# CPU.net
KiCad netlist of a schematic drawn in EAGLE
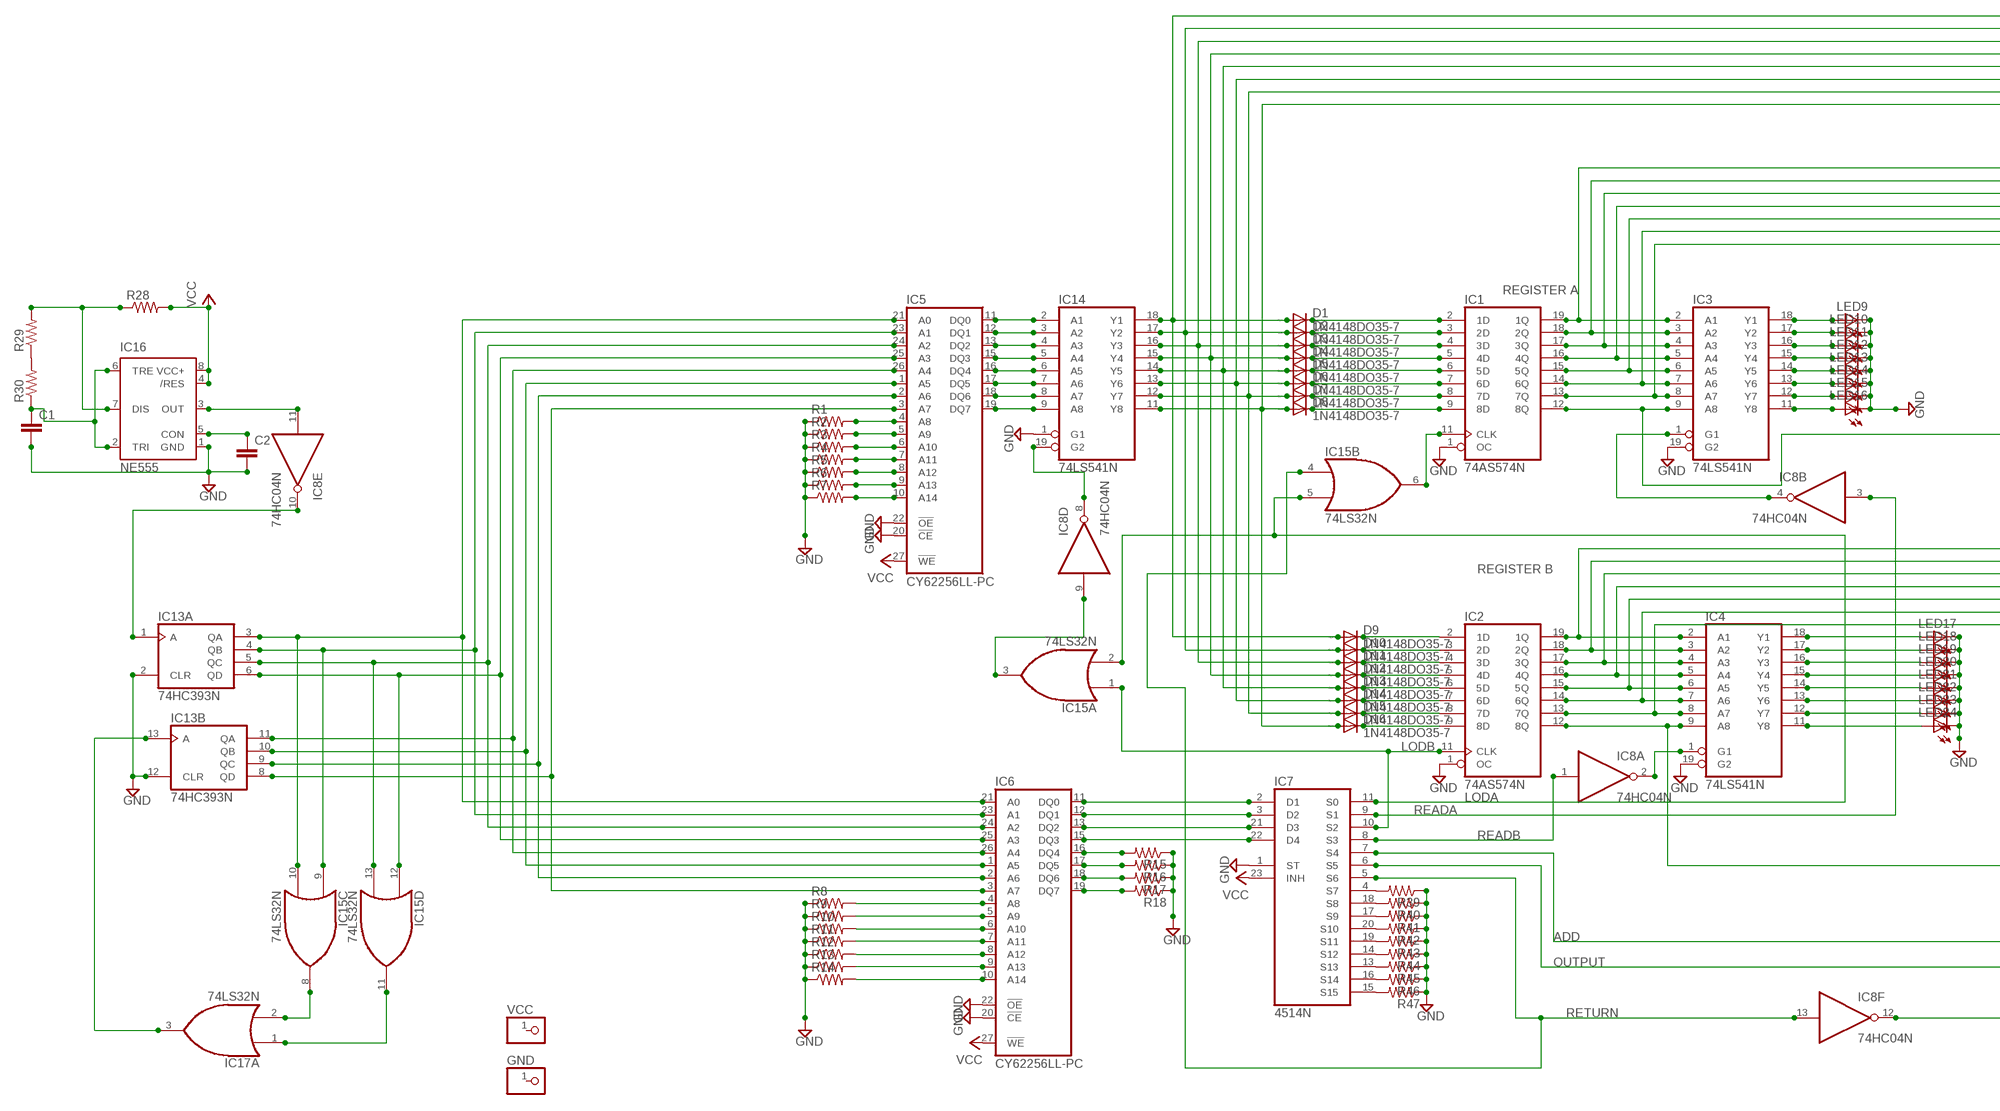
[diagram p0: schematic, sheet 1, part 1 of 2]
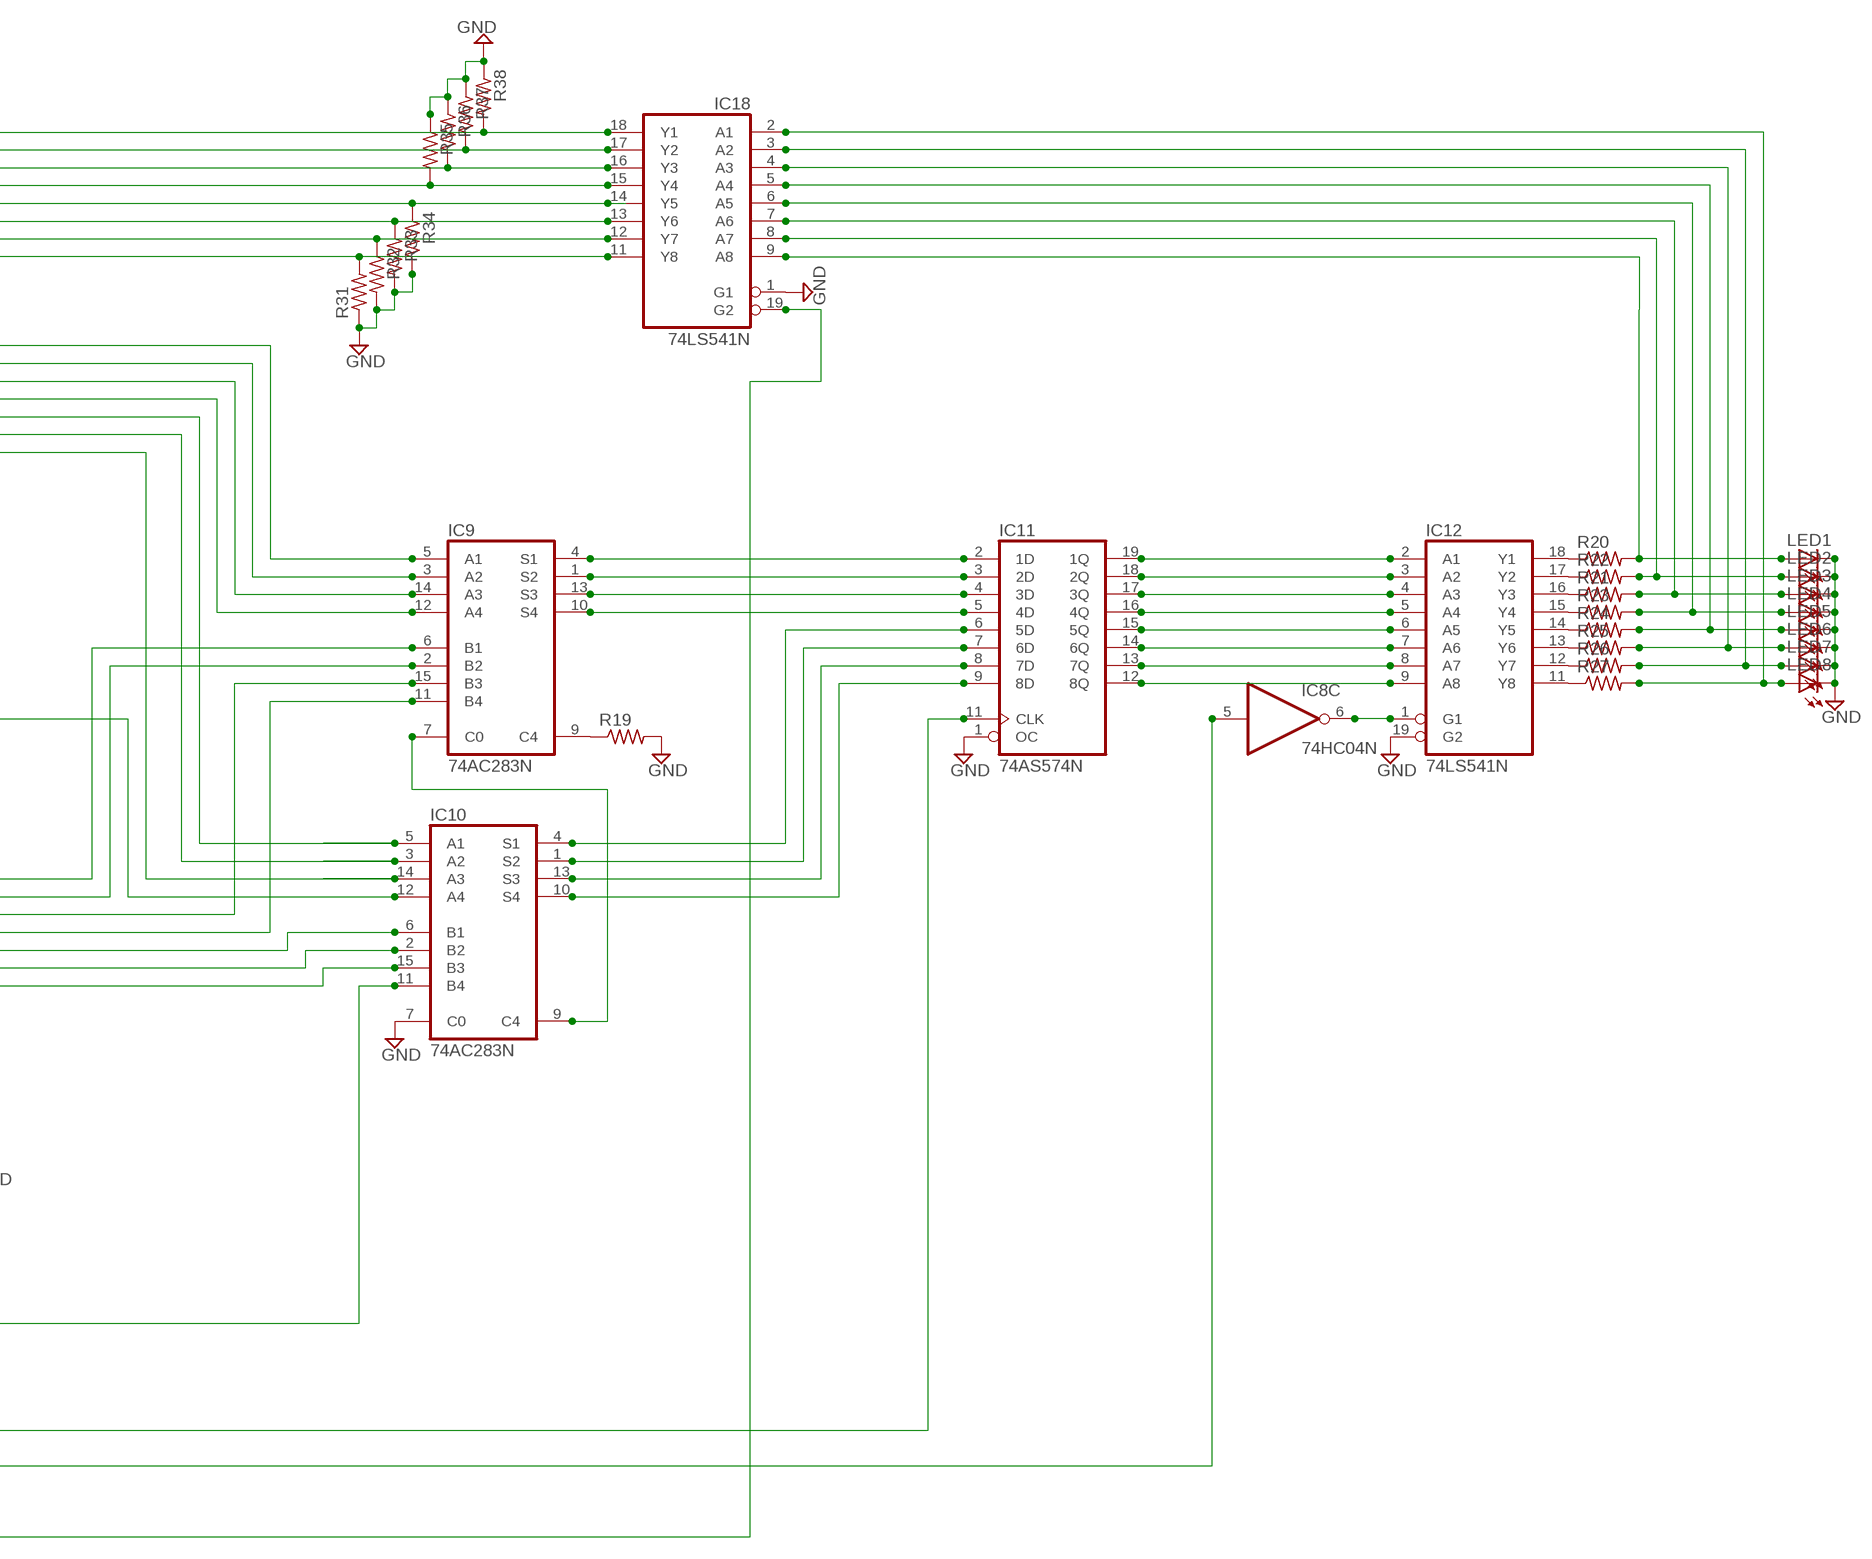
[diagram p1: schematic, sheet 1, part 2 of 2]

(export (version "E")
  (design (tool "Eeschema 10.0.6"))
  (components
    (comp (ref "C1")
      (value "C2,5-3")
      (footprint "eagle-import:C2.5-3")
      (libsource (lib "eagle-import") (part "C2,5-3"))
    )
    (comp (ref "C2")
      (value "C2,5-3")
      (footprint "eagle-import:C2.5-3")
      (libsource (lib "eagle-import") (part "C2,5-3"))
    )
    (comp (ref "D1")
      (value "1N4148DO35-7")
      (footprint "eagle-import:DO35-7")
      (libsource (lib "eagle-import") (part "1N4148DO35-7"))
    )
    (comp (ref "D2")
      (value "1N4148DO35-7")
      (footprint "eagle-import:DO35-7")
      (libsource (lib "eagle-import") (part "1N4148DO35-7"))
    )
    (comp (ref "D3")
      (value "1N4148DO35-7")
      (footprint "eagle-import:DO35-7")
      (libsource (lib "eagle-import") (part "1N4148DO35-7"))
    )
    (comp (ref "D4")
      (value "1N4148DO35-7")
      (footprint "eagle-import:DO35-7")
      (libsource (lib "eagle-import") (part "1N4148DO35-7"))
    )
    (comp (ref "D5")
      (value "1N4148DO35-7")
      (footprint "eagle-import:DO35-7")
      (libsource (lib "eagle-import") (part "1N4148DO35-7"))
    )
    (comp (ref "D6")
      (value "1N4148DO35-7")
      (footprint "eagle-import:DO35-7")
      (libsource (lib "eagle-import") (part "1N4148DO35-7"))
    )
    (comp (ref "D7")
      (value "1N4148DO35-7")
      (footprint "eagle-import:DO35-7")
      (libsource (lib "eagle-import") (part "1N4148DO35-7"))
    )
    (comp (ref "D8")
      (value "1N4148DO35-7")
      (footprint "eagle-import:DO35-7")
      (libsource (lib "eagle-import") (part "1N4148DO35-7"))
    )
    (comp (ref "D9")
      (value "1N4148DO35-7")
      (footprint "eagle-import:DO35-7")
      (libsource (lib "eagle-import") (part "1N4148DO35-7"))
    )
    (comp (ref "D10")
      (value "1N4148DO35-7")
      (footprint "eagle-import:DO35-7")
      (libsource (lib "eagle-import") (part "1N4148DO35-7"))
    )
    (comp (ref "D11")
      (value "1N4148DO35-7")
      (footprint "eagle-import:DO35-7")
      (libsource (lib "eagle-import") (part "1N4148DO35-7"))
    )
    (comp (ref "D12")
      (value "1N4148DO35-7")
      (footprint "eagle-import:DO35-7")
      (libsource (lib "eagle-import") (part "1N4148DO35-7"))
    )
    (comp (ref "D13")
      (value "1N4148DO35-7")
      (footprint "eagle-import:DO35-7")
      (libsource (lib "eagle-import") (part "1N4148DO35-7"))
    )
    (comp (ref "D14")
      (value "1N4148DO35-7")
      (footprint "eagle-import:DO35-7")
      (libsource (lib "eagle-import") (part "1N4148DO35-7"))
    )
    (comp (ref "D15")
      (value "1N4148DO35-7")
      (footprint "eagle-import:DO35-7")
      (libsource (lib "eagle-import") (part "1N4148DO35-7"))
    )
    (comp (ref "D16")
      (value "1N4148DO35-7")
      (footprint "eagle-import:DO35-7")
      (libsource (lib "eagle-import") (part "1N4148DO35-7"))
    )
    (comp (ref "GND")
      (value "PINHD-1X1")
      (footprint "eagle-import:1X01")
      (libsource (lib "eagle-import") (part "PINHD-1X1"))
    )
    (comp (ref "IC1")
      (value "74AS574N")
      (footprint "eagle-import:DIL20")
      (libsource (lib "eagle-import") (part "74574NAS"))
    )
    (comp (ref "IC2")
      (value "74AS574N")
      (footprint "eagle-import:DIL20")
      (libsource (lib "eagle-import") (part "74574NAS"))
    )
    (comp (ref "IC3")
      (value "74LS541N")
      (footprint "eagle-import:DIL20")
      (libsource (lib "eagle-import") (part "74541NLS"))
    )
    (comp (ref "IC4")
      (value "74LS541N")
      (footprint "eagle-import:DIL20")
      (libsource (lib "eagle-import") (part "74541NLS"))
    )
    (comp (ref "IC5")
      (value "CY62256LL-PC")
      (footprint "eagle-import:DIL28-6")
      (libsource (lib "eagle-import") (part "CY62256LL-?PC"))
    )
    (comp (ref "IC6")
      (value "CY62256LL-PC")
      (footprint "eagle-import:DIL28-6")
      (libsource (lib "eagle-import") (part "CY62256LL-?PC"))
    )
    (comp (ref "IC7")
      (value "4514N")
      (footprint "eagle-import:DIL24-6")
      (libsource (lib "eagle-import") (part "4514N"))
    )
    (comp (ref "IC8")
      (value "74HC04N")
      (footprint "eagle-import:DIL14")
      (libsource (lib "eagle-import") (part "7404NHC"))
    )
    (comp (ref "IC9")
      (value "74AC283N")
      (footprint "eagle-import:DIL16")
      (libsource (lib "eagle-import") (part "74283NAC"))
    )
    (comp (ref "IC10")
      (value "74AC283N")
      (footprint "eagle-import:DIL16")
      (libsource (lib "eagle-import") (part "74283NAC"))
    )
    (comp (ref "IC11")
      (value "74AS574N")
      (footprint "eagle-import:DIL20")
      (libsource (lib "eagle-import") (part "74574NAS"))
    )
    (comp (ref "IC12")
      (value "74LS541N")
      (footprint "eagle-import:DIL20")
      (libsource (lib "eagle-import") (part "74541NLS"))
    )
    (comp (ref "IC13")
      (value "74HC393N")
      (footprint "eagle-import:DIL14")
      (libsource (lib "eagle-import") (part "74393NHC"))
    )
    (comp (ref "IC14")
      (value "74LS541N")
      (footprint "eagle-import:DIL20")
      (libsource (lib "eagle-import") (part "74541NLS"))
    )
    (comp (ref "IC15")
      (value "74LS32N")
      (footprint "eagle-import:DIL14")
      (libsource (lib "eagle-import") (part "7432NLS"))
    )
    (comp (ref "IC16")
      (value "NE555")
      (footprint "eagle-import:DIL-08")
      (fields (field (name "MF") "Arrow Electronics") (field (name "MPN") "NE555N"))
      (libsource (lib "eagle-import") (part "NE555"))
    )
    (comp (ref "IC17")
      (value "74LS32N")
      (footprint "eagle-import:DIL14")
      (libsource (lib "eagle-import") (part "7432NLS"))
    )
    (comp (ref "IC18")
      (value "74LS541N")
      (footprint "eagle-import:DIL20")
      (libsource (lib "eagle-import") (part "74541NLS"))
    )
    (comp (ref "LED1")
      (value "LED3MM")
      (footprint "eagle-import:LED3MM")
      (libsource (lib "eagle-import") (part "LED3MM"))
    )
    (comp (ref "LED2")
      (value "LED3MM")
      (footprint "eagle-import:LED3MM")
      (libsource (lib "eagle-import") (part "LED3MM"))
    )
    (comp (ref "LED3")
      (value "LED3MM")
      (footprint "eagle-import:LED3MM")
      (libsource (lib "eagle-import") (part "LED3MM"))
    )
    (comp (ref "LED4")
      (value "LED3MM")
      (footprint "eagle-import:LED3MM")
      (libsource (lib "eagle-import") (part "LED3MM"))
    )
    (comp (ref "LED5")
      (value "LED3MM")
      (footprint "eagle-import:LED3MM")
      (libsource (lib "eagle-import") (part "LED3MM"))
    )
    (comp (ref "LED6")
      (value "LED3MM")
      (footprint "eagle-import:LED3MM")
      (libsource (lib "eagle-import") (part "LED3MM"))
    )
    (comp (ref "LED7")
      (value "LED3MM")
      (footprint "eagle-import:LED3MM")
      (libsource (lib "eagle-import") (part "LED3MM"))
    )
    (comp (ref "LED8")
      (value "LED3MM")
      (footprint "eagle-import:LED3MM")
      (libsource (lib "eagle-import") (part "LED3MM"))
    )
    (comp (ref "LED9")
      (value "LED3MM")
      (footprint "eagle-import:LED3MM")
      (libsource (lib "eagle-import") (part "LED3MM"))
    )
    (comp (ref "LED10")
      (value "LED3MM")
      (footprint "eagle-import:LED3MM")
      (libsource (lib "eagle-import") (part "LED3MM"))
    )
    (comp (ref "LED11")
      (value "LED3MM")
      (footprint "eagle-import:LED3MM")
      (libsource (lib "eagle-import") (part "LED3MM"))
    )
    (comp (ref "LED12")
      (value "LED3MM")
      (footprint "eagle-import:LED3MM")
      (libsource (lib "eagle-import") (part "LED3MM"))
    )
    (comp (ref "LED13")
      (value "LED3MM")
      (footprint "eagle-import:LED3MM")
      (libsource (lib "eagle-import") (part "LED3MM"))
    )
    (comp (ref "LED14")
      (value "LED3MM")
      (footprint "eagle-import:LED3MM")
      (libsource (lib "eagle-import") (part "LED3MM"))
    )
    (comp (ref "LED15")
      (value "LED3MM")
      (footprint "eagle-import:LED3MM")
      (libsource (lib "eagle-import") (part "LED3MM"))
    )
    (comp (ref "LED16")
      (value "LED3MM")
      (footprint "eagle-import:LED3MM")
      (libsource (lib "eagle-import") (part "LED3MM"))
    )
    (comp (ref "LED17")
      (value "LED3MM")
      (footprint "eagle-import:LED3MM")
      (libsource (lib "eagle-import") (part "LED3MM"))
    )
    (comp (ref "LED18")
      (value "LED3MM")
      (footprint "eagle-import:LED3MM")
      (libsource (lib "eagle-import") (part "LED3MM"))
    )
    (comp (ref "LED19")
      (value "LED3MM")
      (footprint "eagle-import:LED3MM")
      (libsource (lib "eagle-import") (part "LED3MM"))
    )
    (comp (ref "LED20")
      (value "LED3MM")
      (footprint "eagle-import:LED3MM")
      (libsource (lib "eagle-import") (part "LED3MM"))
    )
    (comp (ref "LED21")
      (value "LED3MM")
      (footprint "eagle-import:LED3MM")
      (libsource (lib "eagle-import") (part "LED3MM"))
    )
    (comp (ref "LED22")
      (value "LED3MM")
      (footprint "eagle-import:LED3MM")
      (libsource (lib "eagle-import") (part "LED3MM"))
    )
    (comp (ref "LED23")
      (value "LED3MM")
      (footprint "eagle-import:LED3MM")
      (libsource (lib "eagle-import") (part "LED3MM"))
    )
    (comp (ref "LED24")
      (value "LED3MM")
      (footprint "eagle-import:LED3MM")
      (libsource (lib "eagle-import") (part "LED3MM"))
    )
    (comp (ref "R1")
      (value "R-US_MELF0102AX")
      (footprint "eagle-import:MINI_MELF-0102AX")
      (libsource (lib "eagle-import") (part "R-US_MELF0102AX"))
    )
    (comp (ref "R2")
      (value "R-US_MELF0102AX")
      (footprint "eagle-import:MINI_MELF-0102AX")
      (libsource (lib "eagle-import") (part "R-US_MELF0102AX"))
    )
    (comp (ref "R3")
      (value "R-US_MELF0102AX")
      (footprint "eagle-import:MINI_MELF-0102AX")
      (libsource (lib "eagle-import") (part "R-US_MELF0102AX"))
    )
    (comp (ref "R4")
      (value "R-US_MELF0102AX")
      (footprint "eagle-import:MINI_MELF-0102AX")
      (libsource (lib "eagle-import") (part "R-US_MELF0102AX"))
    )
    (comp (ref "R5")
      (value "R-US_MELF0102AX")
      (footprint "eagle-import:MINI_MELF-0102AX")
      (libsource (lib "eagle-import") (part "R-US_MELF0102AX"))
    )
    (comp (ref "R6")
      (value "R-US_MELF0102AX")
      (footprint "eagle-import:MINI_MELF-0102AX")
      (libsource (lib "eagle-import") (part "R-US_MELF0102AX"))
    )
    (comp (ref "R7")
      (value "R-US_MELF0102AX")
      (footprint "eagle-import:MINI_MELF-0102AX")
      (libsource (lib "eagle-import") (part "R-US_MELF0102AX"))
    )
    (comp (ref "R8")
      (value "R-US_MELF0102AX")
      (footprint "eagle-import:MINI_MELF-0102AX")
      (libsource (lib "eagle-import") (part "R-US_MELF0102AX"))
    )
    (comp (ref "R9")
      (value "R-US_MELF0102AX")
      (footprint "eagle-import:MINI_MELF-0102AX")
      (libsource (lib "eagle-import") (part "R-US_MELF0102AX"))
    )
    (comp (ref "R10")
      (value "R-US_MELF0102AX")
      (footprint "eagle-import:MINI_MELF-0102AX")
      (libsource (lib "eagle-import") (part "R-US_MELF0102AX"))
    )
    (comp (ref "R11")
      (value "R-US_MELF0102AX")
      (footprint "eagle-import:MINI_MELF-0102AX")
      (libsource (lib "eagle-import") (part "R-US_MELF0102AX"))
    )
    (comp (ref "R12")
      (value "R-US_MELF0102AX")
      (footprint "eagle-import:MINI_MELF-0102AX")
      (libsource (lib "eagle-import") (part "R-US_MELF0102AX"))
    )
    (comp (ref "R13")
      (value "R-US_MELF0102AX")
      (footprint "eagle-import:MINI_MELF-0102AX")
      (libsource (lib "eagle-import") (part "R-US_MELF0102AX"))
    )
    (comp (ref "R14")
      (value "R-US_MELF0102AX")
      (footprint "eagle-import:MINI_MELF-0102AX")
      (libsource (lib "eagle-import") (part "R-US_MELF0102AX"))
    )
    (comp (ref "R15")
      (value "R-US_MELF0102AX")
      (footprint "eagle-import:MINI_MELF-0102AX")
      (libsource (lib "eagle-import") (part "R-US_MELF0102AX"))
    )
    (comp (ref "R16")
      (value "R-US_MELF0102AX")
      (footprint "eagle-import:MINI_MELF-0102AX")
      (libsource (lib "eagle-import") (part "R-US_MELF0102AX"))
    )
    (comp (ref "R17")
      (value "R-US_MELF0102AX")
      (footprint "eagle-import:MINI_MELF-0102AX")
      (libsource (lib "eagle-import") (part "R-US_MELF0102AX"))
    )
    (comp (ref "R18")
      (value "R-US_MELF0102AX")
      (footprint "eagle-import:MINI_MELF-0102AX")
      (libsource (lib "eagle-import") (part "R-US_MELF0102AX"))
    )
    (comp (ref "R19")
      (value "R-US_MELF0102AX")
      (footprint "eagle-import:MINI_MELF-0102AX")
      (libsource (lib "eagle-import") (part "R-US_MELF0102AX"))
    )
    (comp (ref "R20")
      (value "R-US_MELF0102AX")
      (footprint "eagle-import:MINI_MELF-0102AX")
      (libsource (lib "eagle-import") (part "R-US_MELF0102AX"))
    )
    (comp (ref "R21")
      (value "R-US_MELF0102AX")
      (footprint "eagle-import:MINI_MELF-0102AX")
      (libsource (lib "eagle-import") (part "R-US_MELF0102AX"))
    )
    (comp (ref "R22")
      (value "R-US_MELF0102AX")
      (footprint "eagle-import:MINI_MELF-0102AX")
      (libsource (lib "eagle-import") (part "R-US_MELF0102AX"))
    )
    (comp (ref "R23")
      (value "R-US_MELF0102AX")
      (footprint "eagle-import:MINI_MELF-0102AX")
      (libsource (lib "eagle-import") (part "R-US_MELF0102AX"))
    )
    (comp (ref "R24")
      (value "R-US_MELF0102AX")
      (footprint "eagle-import:MINI_MELF-0102AX")
      (libsource (lib "eagle-import") (part "R-US_MELF0102AX"))
    )
    (comp (ref "R25")
      (value "R-US_MELF0102AX")
      (footprint "eagle-import:MINI_MELF-0102AX")
      (libsource (lib "eagle-import") (part "R-US_MELF0102AX"))
    )
    (comp (ref "R26")
      (value "R-US_MELF0102AX")
      (footprint "eagle-import:MINI_MELF-0102AX")
      (libsource (lib "eagle-import") (part "R-US_MELF0102AX"))
    )
    (comp (ref "R27")
      (value "R-US_MELF0102AX")
      (footprint "eagle-import:MINI_MELF-0102AX")
      (libsource (lib "eagle-import") (part "R-US_MELF0102AX"))
    )
    (comp (ref "R28")
      (value "R-US_MELF0102AX")
      (footprint "eagle-import:MINI_MELF-0102AX")
      (libsource (lib "eagle-import") (part "R-US_MELF0102AX"))
    )
    (comp (ref "R29")
      (value "R-US_MELF0102AX")
      (footprint "eagle-import:MINI_MELF-0102AX")
      (libsource (lib "eagle-import") (part "R-US_MELF0102AX"))
    )
    (comp (ref "R30")
      (value "R-US_MELF0102AX")
      (footprint "eagle-import:MINI_MELF-0102AX")
      (libsource (lib "eagle-import") (part "R-US_MELF0102AX"))
    )
    (comp (ref "R31")
      (value "R-US_MELF0102AX")
      (footprint "eagle-import:MINI_MELF-0102AX")
      (libsource (lib "eagle-import") (part "R-US_MELF0102AX"))
    )
    (comp (ref "R32")
      (value "R-US_MELF0102AX")
      (footprint "eagle-import:MINI_MELF-0102AX")
      (libsource (lib "eagle-import") (part "R-US_MELF0102AX"))
    )
    (comp (ref "R33")
      (value "R-US_MELF0102AX")
      (footprint "eagle-import:MINI_MELF-0102AX")
      (libsource (lib "eagle-import") (part "R-US_MELF0102AX"))
    )
    (comp (ref "R34")
      (value "R-US_MELF0102AX")
      (footprint "eagle-import:MINI_MELF-0102AX")
      (libsource (lib "eagle-import") (part "R-US_MELF0102AX"))
    )
    (comp (ref "R35")
      (value "R-US_MELF0102AX")
      (footprint "eagle-import:MINI_MELF-0102AX")
      (libsource (lib "eagle-import") (part "R-US_MELF0102AX"))
    )
    (comp (ref "R36")
      (value "R-US_MELF0102AX")
      (footprint "eagle-import:MINI_MELF-0102AX")
      (libsource (lib "eagle-import") (part "R-US_MELF0102AX"))
    )
    (comp (ref "R37")
      (value "R-US_MELF0102AX")
      (footprint "eagle-import:MINI_MELF-0102AX")
      (libsource (lib "eagle-import") (part "R-US_MELF0102AX"))
    )
    (comp (ref "R38")
      (value "R-US_MELF0102AX")
      (footprint "eagle-import:MINI_MELF-0102AX")
      (libsource (lib "eagle-import") (part "R-US_MELF0102AX"))
    )
    (comp (ref "R39")
      (value "R-US_MELF0102AX")
      (footprint "eagle-import:MINI_MELF-0102AX")
      (libsource (lib "eagle-import") (part "R-US_MELF0102AX"))
    )
    (comp (ref "R40")
      (value "R-US_MELF0102AX")
      (footprint "eagle-import:MINI_MELF-0102AX")
      (libsource (lib "eagle-import") (part "R-US_MELF0102AX"))
    )
    (comp (ref "R41")
      (value "R-US_MELF0102AX")
      (footprint "eagle-import:MINI_MELF-0102AX")
      (libsource (lib "eagle-import") (part "R-US_MELF0102AX"))
    )
    (comp (ref "R42")
      (value "R-US_MELF0102AX")
      (footprint "eagle-import:MINI_MELF-0102AX")
      (libsource (lib "eagle-import") (part "R-US_MELF0102AX"))
    )
    (comp (ref "R43")
      (value "R-US_MELF0102AX")
      (footprint "eagle-import:MINI_MELF-0102AX")
      (libsource (lib "eagle-import") (part "R-US_MELF0102AX"))
    )
    (comp (ref "R44")
      (value "R-US_MELF0102AX")
      (footprint "eagle-import:MINI_MELF-0102AX")
      (libsource (lib "eagle-import") (part "R-US_MELF0102AX"))
    )
    (comp (ref "R45")
      (value "R-US_MELF0102AX")
      (footprint "eagle-import:MINI_MELF-0102AX")
      (libsource (lib "eagle-import") (part "R-US_MELF0102AX"))
    )
    (comp (ref "R46")
      (value "R-US_MELF0102AX")
      (footprint "eagle-import:MINI_MELF-0102AX")
      (libsource (lib "eagle-import") (part "R-US_MELF0102AX"))
    )
    (comp (ref "R47")
      (value "R-US_MELF0102AX")
      (footprint "eagle-import:MINI_MELF-0102AX")
      (libsource (lib "eagle-import") (part "R-US_MELF0102AX"))
    )
    (comp (ref "VCC")
      (value "PINHD-1X1")
      (footprint "eagle-import:1X01")
      (libsource (lib "eagle-import") (part "PINHD-1X1"))
    )
  )
  (nets
    (net (code "1") (name "GND") (class "Default")
      (node (ref "C1") (pin "2") (pinfunction "2_2") (pintype "passive"))
      (node (ref "C2") (pin "2") (pinfunction "2_2") (pintype "passive"))
      (node (ref "IC1") (pin "1") (pinfunction "OC_1") (pintype "input"))
      (node (ref "IC10") (pin "7") (pinfunction "C0_7") (pintype "input"))
      (node (ref "IC11") (pin "1") (pinfunction "OC_1") (pintype "input"))
      (node (ref "IC12") (pin "19") (pinfunction "G2_19") (pintype "input"))
      (node (ref "IC13") (pin "12") (pinfunction "CLR_12") (pintype "input"))
      (node (ref "IC13") (pin "2") (pinfunction "CLR_2") (pintype "input"))
      (node (ref "IC14") (pin "1") (pinfunction "G1_1") (pintype "input"))
      (node (ref "IC16") (pin "1") (pinfunction "GND_1") (pintype "power_in"))
      (node (ref "IC18") (pin "1") (pinfunction "G1_1") (pintype "input"))
      (node (ref "IC2") (pin "1") (pinfunction "OC_1") (pintype "input"))
      (node (ref "IC3") (pin "19") (pinfunction "G2_19") (pintype "input"))
      (node (ref "IC4") (pin "19") (pinfunction "G2_19") (pintype "input"))
      (node (ref "IC5") (pin "20") (pinfunction "~{CE}_20") (pintype "input"))
      (node (ref "IC5") (pin "22") (pinfunction "~{OE}_22") (pintype "input"))
      (node (ref "IC6") (pin "20") (pinfunction "~{CE}_20") (pintype "input"))
      (node (ref "IC6") (pin "22") (pinfunction "~{OE}_22") (pintype "input"))
      (node (ref "IC7") (pin "1") (pinfunction "ST_1") (pintype "input"))
      (node (ref "LED1") (pin "K") (pinfunction "C_K") (pintype "passive"))
      (node (ref "LED10") (pin "K") (pinfunction "C_K") (pintype "passive"))
      (node (ref "LED11") (pin "K") (pinfunction "C_K") (pintype "passive"))
      (node (ref "LED12") (pin "K") (pinfunction "C_K") (pintype "passive"))
      (node (ref "LED13") (pin "K") (pinfunction "C_K") (pintype "passive"))
      (node (ref "LED14") (pin "K") (pinfunction "C_K") (pintype "passive"))
      (node (ref "LED15") (pin "K") (pinfunction "C_K") (pintype "passive"))
      (node (ref "LED16") (pin "K") (pinfunction "C_K") (pintype "passive"))
      (node (ref "LED17") (pin "K") (pinfunction "C_K") (pintype "passive"))
      (node (ref "LED18") (pin "K") (pinfunction "C_K") (pintype "passive"))
      (node (ref "LED19") (pin "K") (pinfunction "C_K") (pintype "passive"))
      (node (ref "LED2") (pin "K") (pinfunction "C_K") (pintype "passive"))
      (node (ref "LED20") (pin "K") (pinfunction "C_K") (pintype "passive"))
      (node (ref "LED21") (pin "K") (pinfunction "C_K") (pintype "passive"))
      (node (ref "LED22") (pin "K") (pinfunction "C_K") (pintype "passive"))
      (node (ref "LED23") (pin "K") (pinfunction "C_K") (pintype "passive"))
      (node (ref "LED24") (pin "K") (pinfunction "C_K") (pintype "passive"))
      (node (ref "LED3") (pin "K") (pinfunction "C_K") (pintype "passive"))
      (node (ref "LED4") (pin "K") (pinfunction "C_K") (pintype "passive"))
      (node (ref "LED5") (pin "K") (pinfunction "C_K") (pintype "passive"))
      (node (ref "LED6") (pin "K") (pinfunction "C_K") (pintype "passive"))
      (node (ref "LED7") (pin "K") (pinfunction "C_K") (pintype "passive"))
      (node (ref "LED8") (pin "K") (pinfunction "C_K") (pintype "passive"))
      (node (ref "LED9") (pin "K") (pinfunction "C_K") (pintype "passive"))
      (node (ref "R1") (pin "1") (pinfunction "1_1") (pintype "passive"))
      (node (ref "R10") (pin "1") (pinfunction "1_1") (pintype "passive"))
      (node (ref "R11") (pin "1") (pinfunction "1_1") (pintype "passive"))
      (node (ref "R12") (pin "1") (pinfunction "1_1") (pintype "passive"))
      (node (ref "R13") (pin "1") (pinfunction "1_1") (pintype "passive"))
      (node (ref "R14") (pin "1") (pinfunction "1_1") (pintype "passive"))
      (node (ref "R15") (pin "1") (pinfunction "1_1") (pintype "passive"))
      (node (ref "R16") (pin "1") (pinfunction "1_1") (pintype "passive"))
      (node (ref "R17") (pin "1") (pinfunction "1_1") (pintype "passive"))
      (node (ref "R18") (pin "1") (pinfunction "1_1") (pintype "passive"))
      (node (ref "R19") (pin "2") (pinfunction "2_2") (pintype "passive"))
      (node (ref "R2") (pin "1") (pinfunction "1_1") (pintype "passive"))
      (node (ref "R3") (pin "1") (pinfunction "1_1") (pintype "passive"))
      (node (ref "R31") (pin "1") (pinfunction "1_1") (pintype "passive"))
      (node (ref "R32") (pin "2") (pinfunction "2_2") (pintype "passive"))
      (node (ref "R33") (pin "2") (pinfunction "2_2") (pintype "passive"))
      (node (ref "R34") (pin "2") (pinfunction "2_2") (pintype "passive"))
      (node (ref "R35") (pin "1") (pinfunction "1_1") (pintype "passive"))
      (node (ref "R36") (pin "1") (pinfunction "1_1") (pintype "passive"))
      (node (ref "R37") (pin "1") (pinfunction "1_1") (pintype "passive"))
      (node (ref "R38") (pin "1") (pinfunction "1_1") (pintype "passive"))
      (node (ref "R39") (pin "1") (pinfunction "1_1") (pintype "passive"))
      (node (ref "R4") (pin "1") (pinfunction "1_1") (pintype "passive"))
      (node (ref "R40") (pin "1") (pinfunction "1_1") (pintype "passive"))
      (node (ref "R41") (pin "1") (pinfunction "1_1") (pintype "passive"))
      (node (ref "R42") (pin "1") (pinfunction "1_1") (pintype "passive"))
      (node (ref "R43") (pin "1") (pinfunction "1_1") (pintype "passive"))
      (node (ref "R44") (pin "1") (pinfunction "1_1") (pintype "passive"))
      (node (ref "R45") (pin "1") (pinfunction "1_1") (pintype "passive"))
      (node (ref "R46") (pin "1") (pinfunction "1_1") (pintype "passive"))
      (node (ref "R47") (pin "1") (pinfunction "1_1") (pintype "passive"))
      (node (ref "R5") (pin "1") (pinfunction "1_1") (pintype "passive"))
      (node (ref "R6") (pin "1") (pinfunction "1_1") (pintype "passive"))
      (node (ref "R7") (pin "1") (pinfunction "1_1") (pintype "passive"))
      (node (ref "R8") (pin "1") (pinfunction "1_1") (pintype "passive"))
      (node (ref "R9") (pin "1") (pinfunction "1_1") (pintype "passive"))
    )
    (net (code "2") (name "Net-(IC1A-1D)") (class "Default")
      (node (ref "D1") (pin "C") (pinfunction "C_C") (pintype "passive"))
      (node (ref "IC1") (pin "2") (pinfunction "1D_2") (pintype "input"))
    )
    (net (code "3") (name "Net-(IC1A-1Q)") (class "Default")
      (node (ref "IC1") (pin "19") (pinfunction "1Q_19") (pintype "tri_state"))
      (node (ref "IC3") (pin "2") (pinfunction "A1_2") (pintype "input"))
      (node (ref "IC9") (pin "5") (pinfunction "A1_5") (pintype "input"))
    )
    (net (code "4") (name "Net-(IC1A-2D)") (class "Default")
      (node (ref "D2") (pin "C") (pinfunction "C_C") (pintype "passive"))
      (node (ref "IC1") (pin "3") (pinfunction "2D_3") (pintype "input"))
    )
    (net (code "5") (name "Net-(IC1A-2Q)") (class "Default")
      (node (ref "IC1") (pin "18") (pinfunction "2Q_18") (pintype "tri_state"))
      (node (ref "IC3") (pin "3") (pinfunction "A2_3") (pintype "input"))
      (node (ref "IC9") (pin "3") (pinfunction "A2_3") (pintype "input"))
    )
    (net (code "6") (name "Net-(IC1A-3D)") (class "Default")
      (node (ref "D3") (pin "C") (pinfunction "C_C") (pintype "passive"))
      (node (ref "IC1") (pin "4") (pinfunction "3D_4") (pintype "input"))
    )
    (net (code "7") (name "Net-(IC1A-3Q)") (class "Default")
      (node (ref "IC1") (pin "17") (pinfunction "3Q_17") (pintype "tri_state"))
      (node (ref "IC3") (pin "4") (pinfunction "A3_4") (pintype "input"))
      (node (ref "IC9") (pin "14") (pinfunction "A3_14") (pintype "input"))
    )
    (net (code "8") (name "Net-(IC1A-4D)") (class "Default")
      (node (ref "D4") (pin "C") (pinfunction "C_C") (pintype "passive"))
      (node (ref "IC1") (pin "5") (pinfunction "4D_5") (pintype "input"))
    )
    (net (code "9") (name "Net-(IC1A-4Q)") (class "Default")
      (node (ref "IC1") (pin "16") (pinfunction "4Q_16") (pintype "tri_state"))
      (node (ref "IC3") (pin "5") (pinfunction "A4_5") (pintype "input"))
      (node (ref "IC9") (pin "12") (pinfunction "A4_12") (pintype "input"))
    )
    (net (code "10") (name "Net-(IC1A-5D)") (class "Default")
      (node (ref "D5") (pin "C") (pinfunction "C_C") (pintype "passive"))
      (node (ref "IC1") (pin "6") (pinfunction "5D_6") (pintype "input"))
    )
    (net (code "11") (name "Net-(IC1A-6D)") (class "Default")
      (node (ref "D6") (pin "C") (pinfunction "C_C") (pintype "passive"))
      (node (ref "IC1") (pin "7") (pinfunction "6D_7") (pintype "input"))
    )
    (net (code "12") (name "Net-(IC1A-7D)") (class "Default")
      (node (ref "D7") (pin "C") (pinfunction "C_C") (pintype "passive"))
      (node (ref "IC1") (pin "8") (pinfunction "7D_8") (pintype "input"))
    )
    (net (code "13") (name "Net-(IC1A-8D)") (class "Default")
      (node (ref "D8") (pin "C") (pinfunction "C_C") (pintype "passive"))
      (node (ref "IC1") (pin "9") (pinfunction "8D_9") (pintype "input"))
    )
    (net (code "14") (name "Net-(IC2A-1D)") (class "Default")
      (node (ref "D9") (pin "C") (pinfunction "C_C") (pintype "passive"))
      (node (ref "IC2") (pin "2") (pinfunction "1D_2") (pintype "input"))
    )
    (net (code "15") (name "Net-(IC2A-1Q)") (class "Default")
      (node (ref "IC2") (pin "19") (pinfunction "1Q_19") (pintype "tri_state"))
      (node (ref "IC4") (pin "2") (pinfunction "A1_2") (pintype "input"))
      (node (ref "IC9") (pin "6") (pinfunction "B1_6") (pintype "input"))
    )
    (net (code "16") (name "Net-(IC2A-2D)") (class "Default")
      (node (ref "D10") (pin "C") (pinfunction "C_C") (pintype "passive"))
      (node (ref "IC2") (pin "3") (pinfunction "2D_3") (pintype "input"))
    )
    (net (code "17") (name "Net-(IC2A-2Q)") (class "Default")
      (node (ref "IC2") (pin "18") (pinfunction "2Q_18") (pintype "tri_state"))
      (node (ref "IC4") (pin "3") (pinfunction "A2_3") (pintype "input"))
      (node (ref "IC9") (pin "2") (pinfunction "B2_2") (pintype "input"))
    )
    (net (code "18") (name "Net-(IC2A-3D)") (class "Default")
      (node (ref "D11") (pin "C") (pinfunction "C_C") (pintype "passive"))
      (node (ref "IC2") (pin "4") (pinfunction "3D_4") (pintype "input"))
    )
    (net (code "19") (name "Net-(IC2A-3Q)") (class "Default")
      (node (ref "IC2") (pin "17") (pinfunction "3Q_17") (pintype "tri_state"))
      (node (ref "IC4") (pin "4") (pinfunction "A3_4") (pintype "input"))
      (node (ref "IC9") (pin "15") (pinfunction "B3_15") (pintype "input"))
    )
    (net (code "20") (name "Net-(IC2A-4D)") (class "Default")
      (node (ref "D12") (pin "C") (pinfunction "C_C") (pintype "passive"))
      (node (ref "IC2") (pin "5") (pinfunction "4D_5") (pintype "input"))
    )
    (net (code "21") (name "Net-(IC2A-4Q)") (class "Default")
      (node (ref "IC2") (pin "16") (pinfunction "4Q_16") (pintype "tri_state"))
      (node (ref "IC4") (pin "5") (pinfunction "A4_5") (pintype "input"))
      (node (ref "IC9") (pin "11") (pinfunction "B4_11") (pintype "input"))
    )
    (net (code "22") (name "Net-(IC2A-5D)") (class "Default")
      (node (ref "D13") (pin "C") (pinfunction "C_C") (pintype "passive"))
      (node (ref "IC2") (pin "6") (pinfunction "5D_6") (pintype "input"))
    )
    (net (code "23") (name "Net-(IC2A-6D)") (class "Default")
      (node (ref "D14") (pin "C") (pinfunction "C_C") (pintype "passive"))
      (node (ref "IC2") (pin "7") (pinfunction "6D_7") (pintype "input"))
    )
    (net (code "24") (name "Net-(IC2A-7D)") (class "Default")
      (node (ref "D15") (pin "C") (pinfunction "C_C") (pintype "passive"))
      (node (ref "IC2") (pin "8") (pinfunction "7D_8") (pintype "input"))
    )
    (net (code "25") (name "Net-(IC2A-8D)") (class "Default")
      (node (ref "D16") (pin "C") (pinfunction "C_C") (pintype "passive"))
      (node (ref "IC2") (pin "9") (pinfunction "8D_9") (pintype "input"))
    )
    (net (code "26") (name "Net-(IC3A-G1)") (class "Default")
      (node (ref "IC3") (pin "1") (pinfunction "G1_1") (pintype "input"))
      (node (ref "IC8") (pin "4") (pinfunction "O_4") (pintype "output"))
    )
    (net (code "27") (name "Net-(IC3A-Y1)") (class "Default")
      (node (ref "IC3") (pin "18") (pinfunction "Y1_18") (pintype "tri_state"))
      (node (ref "LED9") (pin "A") (pinfunction "A_A") (pintype "passive"))
    )
    (net (code "28") (name "Net-(IC3A-Y2)") (class "Default")
      (node (ref "IC3") (pin "17") (pinfunction "Y2_17") (pintype "tri_state"))
      (node (ref "LED10") (pin "A") (pinfunction "A_A") (pintype "passive"))
    )
    (net (code "29") (name "Net-(IC3A-Y3)") (class "Default")
      (node (ref "IC3") (pin "16") (pinfunction "Y3_16") (pintype "tri_state"))
      (node (ref "LED11") (pin "A") (pinfunction "A_A") (pintype "passive"))
    )
    (net (code "30") (name "Net-(IC3A-Y4)") (class "Default")
      (node (ref "IC3") (pin "15") (pinfunction "Y4_15") (pintype "tri_state"))
      (node (ref "LED12") (pin "A") (pinfunction "A_A") (pintype "passive"))
    )
    (net (code "31") (name "Net-(IC3A-Y5)") (class "Default")
      (node (ref "IC3") (pin "14") (pinfunction "Y5_14") (pintype "tri_state"))
      (node (ref "LED13") (pin "A") (pinfunction "A_A") (pintype "passive"))
    )
    (net (code "32") (name "Net-(IC3A-Y6)") (class "Default")
      (node (ref "IC3") (pin "13") (pinfunction "Y6_13") (pintype "tri_state"))
      (node (ref "LED14") (pin "A") (pinfunction "A_A") (pintype "passive"))
    )
    (net (code "33") (name "Net-(IC3A-Y7)") (class "Default")
      (node (ref "IC3") (pin "12") (pinfunction "Y7_12") (pintype "tri_state"))
      (node (ref "LED15") (pin "A") (pinfunction "A_A") (pintype "passive"))
    )
    (net (code "34") (name "Net-(IC3A-Y8)") (class "Default")
      (node (ref "IC3") (pin "11") (pinfunction "Y8_11") (pintype "tri_state"))
      (node (ref "LED16") (pin "A") (pinfunction "A_A") (pintype "passive"))
    )
    (net (code "35") (name "Net-(IC4A-G1)") (class "Default")
      (node (ref "IC4") (pin "1") (pinfunction "G1_1") (pintype "input"))
      (node (ref "IC8") (pin "2") (pinfunction "O_2") (pintype "output"))
    )
    (net (code "36") (name "Net-(IC4A-Y1)") (class "Default")
      (node (ref "IC4") (pin "18") (pinfunction "Y1_18") (pintype "tri_state"))
      (node (ref "LED17") (pin "A") (pinfunction "A_A") (pintype "passive"))
    )
    (net (code "37") (name "Net-(IC4A-Y2)") (class "Default")
      (node (ref "IC4") (pin "17") (pinfunction "Y2_17") (pintype "tri_state"))
      (node (ref "LED18") (pin "A") (pinfunction "A_A") (pintype "passive"))
    )
    (net (code "38") (name "Net-(IC4A-Y3)") (class "Default")
      (node (ref "IC4") (pin "16") (pinfunction "Y3_16") (pintype "tri_state"))
      (node (ref "LED19") (pin "A") (pinfunction "A_A") (pintype "passive"))
    )
    (net (code "39") (name "Net-(IC4A-Y4)") (class "Default")
      (node (ref "IC4") (pin "15") (pinfunction "Y4_15") (pintype "tri_state"))
      (node (ref "LED20") (pin "A") (pinfunction "A_A") (pintype "passive"))
    )
    (net (code "40") (name "Net-(IC4A-Y5)") (class "Default")
      (node (ref "IC4") (pin "14") (pinfunction "Y5_14") (pintype "tri_state"))
      (node (ref "LED21") (pin "A") (pinfunction "A_A") (pintype "passive"))
    )
    (net (code "41") (name "Net-(IC4A-Y6)") (class "Default")
      (node (ref "IC4") (pin "13") (pinfunction "Y6_13") (pintype "tri_state"))
      (node (ref "LED22") (pin "A") (pinfunction "A_A") (pintype "passive"))
    )
    (net (code "42") (name "Net-(IC4A-Y7)") (class "Default")
      (node (ref "IC4") (pin "12") (pinfunction "Y7_12") (pintype "tri_state"))
      (node (ref "LED23") (pin "A") (pinfunction "A_A") (pintype "passive"))
    )
    (net (code "43") (name "Net-(IC4A-Y8)") (class "Default")
      (node (ref "IC4") (pin "11") (pinfunction "Y8_11") (pintype "tri_state"))
      (node (ref "LED24") (pin "A") (pinfunction "A_A") (pintype "passive"))
    )
    (net (code "44") (name "Net-(IC5A-A8)") (class "Default")
      (node (ref "IC5") (pin "4") (pinfunction "A8_4") (pintype "input"))
      (node (ref "R1") (pin "2") (pinfunction "2_2") (pintype "passive"))
    )
    (net (code "45") (name "Net-(IC5A-A9)") (class "Default")
      (node (ref "IC5") (pin "5") (pinfunction "A9_5") (pintype "input"))
      (node (ref "R2") (pin "2") (pinfunction "2_2") (pintype "passive"))
    )
    (net (code "46") (name "Net-(IC5A-A10)") (class "Default")
      (node (ref "IC5") (pin "6") (pinfunction "A10_6") (pintype "input"))
      (node (ref "R3") (pin "2") (pinfunction "2_2") (pintype "passive"))
    )
    (net (code "47") (name "Net-(IC5A-A11)") (class "Default")
      (node (ref "IC5") (pin "7") (pinfunction "A11_7") (pintype "input"))
      (node (ref "R4") (pin "2") (pinfunction "2_2") (pintype "passive"))
    )
    (net (code "48") (name "Net-(IC5A-A12)") (class "Default")
      (node (ref "IC5") (pin "8") (pinfunction "A12_8") (pintype "input"))
      (node (ref "R5") (pin "2") (pinfunction "2_2") (pintype "passive"))
    )
    (net (code "49") (name "Net-(IC5A-A13)") (class "Default")
      (node (ref "IC5") (pin "9") (pinfunction "A13_9") (pintype "input"))
      (node (ref "R6") (pin "2") (pinfunction "2_2") (pintype "passive"))
    )
    (net (code "50") (name "Net-(IC5A-A14)") (class "Default")
      (node (ref "IC5") (pin "10") (pinfunction "A14_10") (pintype "input"))
      (node (ref "R7") (pin "2") (pinfunction "2_2") (pintype "passive"))
    )
    (net (code "51") (name "Net-(IC6A-A8)") (class "Default")
      (node (ref "IC6") (pin "4") (pinfunction "A8_4") (pintype "input"))
      (node (ref "R8") (pin "2") (pinfunction "2_2") (pintype "passive"))
    )
    (net (code "52") (name "Net-(IC6A-A9)") (class "Default")
      (node (ref "IC6") (pin "5") (pinfunction "A9_5") (pintype "input"))
      (node (ref "R9") (pin "2") (pinfunction "2_2") (pintype "passive"))
    )
    (net (code "53") (name "Net-(IC6A-A10)") (class "Default")
      (node (ref "IC6") (pin "6") (pinfunction "A10_6") (pintype "input"))
      (node (ref "R10") (pin "2") (pinfunction "2_2") (pintype "passive"))
    )
    (net (code "54") (name "Net-(IC6A-A11)") (class "Default")
      (node (ref "IC6") (pin "7") (pinfunction "A11_7") (pintype "input"))
      (node (ref "R11") (pin "2") (pinfunction "2_2") (pintype "passive"))
    )
    (net (code "55") (name "Net-(IC6A-A12)") (class "Default")
      (node (ref "IC6") (pin "8") (pinfunction "A12_8") (pintype "input"))
      (node (ref "R12") (pin "2") (pinfunction "2_2") (pintype "passive"))
    )
    (net (code "56") (name "Net-(IC6A-A13)") (class "Default")
      (node (ref "IC6") (pin "9") (pinfunction "A13_9") (pintype "input"))
      (node (ref "R13") (pin "2") (pinfunction "2_2") (pintype "passive"))
    )
    (net (code "57") (name "Net-(IC6A-A14)") (class "Default")
      (node (ref "IC6") (pin "10") (pinfunction "A14_10") (pintype "input"))
      (node (ref "R14") (pin "2") (pinfunction "2_2") (pintype "passive"))
    )
    (net (code "58") (name "Net-(IC6A-DQ0)") (class "Default")
      (node (ref "IC6") (pin "11") (pinfunction "DQ0_11") (pintype "bidirectional"))
      (node (ref "IC7") (pin "2") (pinfunction "D1_2") (pintype "input"))
    )
    (net (code "59") (name "Net-(IC6A-DQ1)") (class "Default")
      (node (ref "IC6") (pin "12") (pinfunction "DQ1_12") (pintype "bidirectional"))
      (node (ref "IC7") (pin "3") (pinfunction "D2_3") (pintype "input"))
    )
    (net (code "60") (name "Net-(IC6A-DQ2)") (class "Default")
      (node (ref "IC6") (pin "13") (pinfunction "DQ2_13") (pintype "bidirectional"))
      (node (ref "IC7") (pin "21") (pinfunction "D3_21") (pintype "input"))
    )
    (net (code "61") (name "Net-(IC6A-DQ3)") (class "Default")
      (node (ref "IC6") (pin "15") (pinfunction "DQ3_15") (pintype "bidirectional"))
      (node (ref "IC7") (pin "22") (pinfunction "D4_22") (pintype "input"))
    )
    (net (code "62") (name "Net-(IC6A-DQ4)") (class "Default")
      (node (ref "IC6") (pin "16") (pinfunction "DQ4_16") (pintype "bidirectional"))
      (node (ref "R15") (pin "2") (pinfunction "2_2") (pintype "passive"))
    )
    (net (code "63") (name "Net-(IC6A-DQ5)") (class "Default")
      (node (ref "IC6") (pin "17") (pinfunction "DQ5_17") (pintype "bidirectional"))
      (node (ref "R16") (pin "2") (pinfunction "2_2") (pintype "passive"))
    )
    (net (code "64") (name "Net-(IC6A-DQ6)") (class "Default")
      (node (ref "IC6") (pin "18") (pinfunction "DQ6_18") (pintype "bidirectional"))
      (node (ref "R17") (pin "2") (pinfunction "2_2") (pintype "passive"))
    )
    (net (code "65") (name "Net-(IC6A-DQ7)") (class "Default")
      (node (ref "IC6") (pin "19") (pinfunction "DQ7_19") (pintype "bidirectional"))
      (node (ref "R18") (pin "2") (pinfunction "2_2") (pintype "passive"))
    )
    (net (code "66") (name "Net-(IC7A-S1)") (class "Default")
      (node (ref "IC7") (pin "9") (pinfunction "S1_9") (pintype "output"))
      (node (ref "IC8") (pin "3") (pinfunction "I_3") (pintype "input"))
    )
    (net (code "67") (name "Net-(IC7A-S3)") (class "Default")
      (node (ref "IC7") (pin "8") (pinfunction "S3_8") (pintype "output"))
      (node (ref "IC8") (pin "1") (pinfunction "I_1") (pintype "input"))
    )
    (net (code "68") (name "Net-(IC7A-S5)") (class "Default")
      (node (ref "IC7") (pin "6") (pinfunction "S5_6") (pintype "output"))
      (node (ref "IC8") (pin "5") (pinfunction "I_5") (pintype "input"))
    )
    (net (code "69") (name "Net-(IC7A-S7)") (class "Default")
      (node (ref "IC7") (pin "4") (pinfunction "S7_4") (pintype "output"))
      (node (ref "R39") (pin "2") (pinfunction "2_2") (pintype "passive"))
    )
    (net (code "70") (name "Net-(IC7A-S8)") (class "Default")
      (node (ref "IC7") (pin "18") (pinfunction "S8_18") (pintype "output"))
      (node (ref "R40") (pin "2") (pinfunction "2_2") (pintype "passive"))
    )
    (net (code "71") (name "Net-(IC7A-S9)") (class "Default")
      (node (ref "IC7") (pin "17") (pinfunction "S9_17") (pintype "output"))
      (node (ref "R41") (pin "2") (pinfunction "2_2") (pintype "passive"))
    )
    (net (code "72") (name "Net-(IC7A-S10)") (class "Default")
      (node (ref "IC7") (pin "20") (pinfunction "S10_20") (pintype "output"))
      (node (ref "R42") (pin "2") (pinfunction "2_2") (pintype "passive"))
    )
    (net (code "73") (name "Net-(IC7A-S11)") (class "Default")
      (node (ref "IC7") (pin "19") (pinfunction "S11_19") (pintype "output"))
      (node (ref "R43") (pin "2") (pinfunction "2_2") (pintype "passive"))
    )
    (net (code "74") (name "Net-(IC7A-S12)") (class "Default")
      (node (ref "IC7") (pin "14") (pinfunction "S12_14") (pintype "output"))
      (node (ref "R44") (pin "2") (pinfunction "2_2") (pintype "passive"))
    )
    (net (code "75") (name "Net-(IC7A-S13)") (class "Default")
      (node (ref "IC7") (pin "13") (pinfunction "S13_13") (pintype "output"))
      (node (ref "R45") (pin "2") (pinfunction "2_2") (pintype "passive"))
    )
    (net (code "76") (name "Net-(IC7A-S14)") (class "Default")
      (node (ref "IC7") (pin "16") (pinfunction "S14_16") (pintype "output"))
      (node (ref "R46") (pin "2") (pinfunction "2_2") (pintype "passive"))
    )
    (net (code "77") (name "Net-(IC7A-S15)") (class "Default")
      (node (ref "IC7") (pin "15") (pinfunction "S15_15") (pintype "output"))
      (node (ref "R47") (pin "2") (pinfunction "2_2") (pintype "passive"))
    )
    (net (code "78") (name "Net-(IC9A-C4)") (class "Default")
      (node (ref "IC9") (pin "9") (pinfunction "C4_9") (pintype "output"))
      (node (ref "R19") (pin "1") (pinfunction "1_1") (pintype "passive"))
    )
    (net (code "79") (name "Net-(IC10A-A1)") (class "Default")
      (node (ref "IC1") (pin "15") (pinfunction "5Q_15") (pintype "tri_state"))
      (node (ref "IC10") (pin "5") (pinfunction "A1_5") (pintype "input"))
      (node (ref "IC3") (pin "6") (pinfunction "A5_6") (pintype "input"))
    )
    (net (code "80") (name "Net-(IC10A-A2)") (class "Default")
      (node (ref "IC1") (pin "14") (pinfunction "6Q_14") (pintype "tri_state"))
      (node (ref "IC10") (pin "3") (pinfunction "A2_3") (pintype "input"))
      (node (ref "IC3") (pin "7") (pinfunction "A6_7") (pintype "input"))
    )
    (net (code "81") (name "Net-(IC10A-A3)") (class "Default")
      (node (ref "IC1") (pin "13") (pinfunction "7Q_13") (pintype "tri_state"))
      (node (ref "IC10") (pin "14") (pinfunction "A3_14") (pintype "input"))
      (node (ref "IC3") (pin "8") (pinfunction "A7_8") (pintype "input"))
    )
    (net (code "82") (name "Net-(IC10A-A4)") (class "Default")
      (node (ref "IC1") (pin "12") (pinfunction "8Q_12") (pintype "tri_state"))
      (node (ref "IC10") (pin "12") (pinfunction "A4_12") (pintype "input"))
      (node (ref "IC3") (pin "9") (pinfunction "A8_9") (pintype "input"))
    )
    (net (code "83") (name "Net-(IC10A-B1)") (class "Default")
      (node (ref "IC10") (pin "6") (pinfunction "B1_6") (pintype "input"))
      (node (ref "IC2") (pin "15") (pinfunction "5Q_15") (pintype "tri_state"))
      (node (ref "IC4") (pin "6") (pinfunction "A5_6") (pintype "input"))
    )
    (net (code "84") (name "Net-(IC10A-B2)") (class "Default")
      (node (ref "IC10") (pin "2") (pinfunction "B2_2") (pintype "input"))
      (node (ref "IC2") (pin "14") (pinfunction "6Q_14") (pintype "tri_state"))
      (node (ref "IC4") (pin "7") (pinfunction "A6_7") (pintype "input"))
    )
    (net (code "85") (name "Net-(IC10A-B3)") (class "Default")
      (node (ref "IC10") (pin "15") (pinfunction "B3_15") (pintype "input"))
      (node (ref "IC2") (pin "13") (pinfunction "7Q_13") (pintype "tri_state"))
      (node (ref "IC4") (pin "8") (pinfunction "A7_8") (pintype "input"))
    )
    (net (code "86") (name "Net-(IC10A-B4)") (class "Default")
      (node (ref "IC10") (pin "11") (pinfunction "B4_11") (pintype "input"))
      (node (ref "IC2") (pin "12") (pinfunction "8Q_12") (pintype "tri_state"))
      (node (ref "IC4") (pin "9") (pinfunction "A8_9") (pintype "input"))
    )
    (net (code "87") (name "Net-(IC10A-C4)") (class "Default")
      (node (ref "IC10") (pin "9") (pinfunction "C4_9") (pintype "output"))
      (node (ref "IC9") (pin "7") (pinfunction "C0_7") (pintype "input"))
    )
    (net (code "88") (name "Net-(IC10A-S1)") (class "Default")
      (node (ref "IC10") (pin "4") (pinfunction "S1_4") (pintype "output"))
      (node (ref "IC11") (pin "6") (pinfunction "5D_6") (pintype "input"))
    )
    (net (code "89") (name "Net-(IC10A-S2)") (class "Default")
      (node (ref "IC10") (pin "1") (pinfunction "S2_1") (pintype "output"))
      (node (ref "IC11") (pin "7") (pinfunction "6D_7") (pintype "input"))
    )
    (net (code "90") (name "Net-(IC10A-S3)") (class "Default")
      (node (ref "IC10") (pin "13") (pinfunction "S3_13") (pintype "output"))
      (node (ref "IC11") (pin "8") (pinfunction "7D_8") (pintype "input"))
    )
    (net (code "91") (name "Net-(IC10A-S4)") (class "Default")
      (node (ref "IC10") (pin "10") (pinfunction "S4_10") (pintype "output"))
      (node (ref "IC11") (pin "9") (pinfunction "8D_9") (pintype "input"))
    )
    (net (code "92") (name "Net-(IC11A-1D)") (class "Default")
      (node (ref "IC11") (pin "2") (pinfunction "1D_2") (pintype "input"))
      (node (ref "IC9") (pin "4") (pinfunction "S1_4") (pintype "output"))
    )
    (net (code "93") (name "Net-(IC11A-1Q)") (class "Default")
      (node (ref "IC11") (pin "19") (pinfunction "1Q_19") (pintype "tri_state"))
      (node (ref "IC12") (pin "2") (pinfunction "A1_2") (pintype "input"))
    )
    (net (code "94") (name "Net-(IC11A-2D)") (class "Default")
      (node (ref "IC11") (pin "3") (pinfunction "2D_3") (pintype "input"))
      (node (ref "IC9") (pin "1") (pinfunction "S2_1") (pintype "output"))
    )
    (net (code "95") (name "Net-(IC11A-2Q)") (class "Default")
      (node (ref "IC11") (pin "18") (pinfunction "2Q_18") (pintype "tri_state"))
      (node (ref "IC12") (pin "3") (pinfunction "A2_3") (pintype "input"))
    )
    (net (code "96") (name "Net-(IC11A-3D)") (class "Default")
      (node (ref "IC11") (pin "4") (pinfunction "3D_4") (pintype "input"))
      (node (ref "IC9") (pin "13") (pinfunction "S3_13") (pintype "output"))
    )
    (net (code "97") (name "Net-(IC11A-3Q)") (class "Default")
      (node (ref "IC11") (pin "17") (pinfunction "3Q_17") (pintype "tri_state"))
      (node (ref "IC12") (pin "4") (pinfunction "A3_4") (pintype "input"))
    )
    (net (code "98") (name "Net-(IC11A-4D)") (class "Default")
      (node (ref "IC11") (pin "5") (pinfunction "4D_5") (pintype "input"))
      (node (ref "IC9") (pin "10") (pinfunction "S4_10") (pintype "output"))
    )
    (net (code "99") (name "Net-(IC11A-4Q)") (class "Default")
      (node (ref "IC11") (pin "16") (pinfunction "4Q_16") (pintype "tri_state"))
      (node (ref "IC12") (pin "5") (pinfunction "A4_5") (pintype "input"))
    )
    (net (code "100") (name "Net-(IC11A-5Q)") (class "Default")
      (node (ref "IC11") (pin "15") (pinfunction "5Q_15") (pintype "tri_state"))
      (node (ref "IC12") (pin "6") (pinfunction "A5_6") (pintype "input"))
    )
    (net (code "101") (name "Net-(IC11A-6Q)") (class "Default")
      (node (ref "IC11") (pin "14") (pinfunction "6Q_14") (pintype "tri_state"))
      (node (ref "IC12") (pin "7") (pinfunction "A6_7") (pintype "input"))
    )
    (net (code "102") (name "Net-(IC11A-7Q)") (class "Default")
      (node (ref "IC11") (pin "13") (pinfunction "7Q_13") (pintype "tri_state"))
      (node (ref "IC12") (pin "8") (pinfunction "A7_8") (pintype "input"))
    )
    (net (code "103") (name "Net-(IC11A-8Q)") (class "Default")
      (node (ref "IC11") (pin "12") (pinfunction "8Q_12") (pintype "tri_state"))
      (node (ref "IC12") (pin "9") (pinfunction "A8_9") (pintype "input"))
    )
    (net (code "104") (name "Net-(IC11A-CLK)") (class "Default")
      (node (ref "IC11") (pin "11") (pinfunction "CLK_11") (pintype "input"))
      (node (ref "IC7") (pin "7") (pinfunction "S4_7") (pintype "output"))
    )
    (net (code "105") (name "Net-(IC12A-G1)") (class "Default")
      (node (ref "IC12") (pin "1") (pinfunction "G1_1") (pintype "input"))
      (node (ref "IC8") (pin "6") (pinfunction "O_6") (pintype "output"))
    )
    (net (code "106") (name "Net-(IC12A-Y1)") (class "Default")
      (node (ref "IC12") (pin "18") (pinfunction "Y1_18") (pintype "tri_state"))
      (node (ref "R20") (pin "1") (pinfunction "1_1") (pintype "passive"))
    )
    (net (code "107") (name "Net-(IC12A-Y2)") (class "Default")
      (node (ref "IC12") (pin "17") (pinfunction "Y2_17") (pintype "tri_state"))
      (node (ref "R22") (pin "1") (pinfunction "1_1") (pintype "passive"))
    )
    (net (code "108") (name "Net-(IC12A-Y3)") (class "Default")
      (node (ref "IC12") (pin "16") (pinfunction "Y3_16") (pintype "tri_state"))
      (node (ref "R21") (pin "1") (pinfunction "1_1") (pintype "passive"))
    )
    (net (code "109") (name "Net-(IC12A-Y4)") (class "Default")
      (node (ref "IC12") (pin "15") (pinfunction "Y4_15") (pintype "tri_state"))
      (node (ref "R23") (pin "1") (pinfunction "1_1") (pintype "passive"))
    )
    (net (code "110") (name "Net-(IC12A-Y5)") (class "Default")
      (node (ref "IC12") (pin "14") (pinfunction "Y5_14") (pintype "tri_state"))
      (node (ref "R24") (pin "1") (pinfunction "1_1") (pintype "passive"))
    )
    (net (code "111") (name "Net-(IC12A-Y6)") (class "Default")
      (node (ref "IC12") (pin "13") (pinfunction "Y6_13") (pintype "tri_state"))
      (node (ref "R25") (pin "1") (pinfunction "1_1") (pintype "passive"))
    )
    (net (code "112") (name "Net-(IC12A-Y7)") (class "Default")
      (node (ref "IC12") (pin "12") (pinfunction "Y7_12") (pintype "tri_state"))
      (node (ref "R26") (pin "1") (pinfunction "1_1") (pintype "passive"))
    )
    (net (code "113") (name "Net-(IC12A-Y8)") (class "Default")
      (node (ref "IC12") (pin "11") (pinfunction "Y8_11") (pintype "tri_state"))
      (node (ref "R27") (pin "1") (pinfunction "1_1") (pintype "passive"))
    )
    (net (code "114") (name "Net-(IC13A-A)") (class "Default")
      (node (ref "IC13") (pin "1") (pinfunction "A_1") (pintype "input"))
      (node (ref "IC8") (pin "10") (pinfunction "O_10") (pintype "output"))
    )
    (net (code "115") (name "Net-(IC13A-QA)") (class "Default")
      (node (ref "IC13") (pin "3") (pinfunction "QA_3") (pintype "output"))
      (node (ref "IC15") (pin "10") (pinfunction "I1_10") (pintype "input"))
      (node (ref "IC5") (pin "21") (pinfunction "A0_21") (pintype "input"))
      (node (ref "IC6") (pin "21") (pinfunction "A0_21") (pintype "input"))
    )
    (net (code "116") (name "Net-(IC13A-QB)") (class "Default")
      (node (ref "IC13") (pin "4") (pinfunction "QB_4") (pintype "output"))
      (node (ref "IC15") (pin "9") (pinfunction "I0_9") (pintype "input"))
      (node (ref "IC5") (pin "23") (pinfunction "A1_23") (pintype "input"))
      (node (ref "IC6") (pin "23") (pinfunction "A1_23") (pintype "input"))
    )
    (net (code "117") (name "Net-(IC13A-QC)") (class "Default")
      (node (ref "IC13") (pin "5") (pinfunction "QC_5") (pintype "output"))
      (node (ref "IC15") (pin "13") (pinfunction "I1_13") (pintype "input"))
      (node (ref "IC5") (pin "24") (pinfunction "A2_24") (pintype "input"))
      (node (ref "IC6") (pin "24") (pinfunction "A2_24") (pintype "input"))
    )
    (net (code "118") (name "Net-(IC13A-QD)") (class "Default")
      (node (ref "IC13") (pin "6") (pinfunction "QD_6") (pintype "output"))
      (node (ref "IC15") (pin "12") (pinfunction "I0_12") (pintype "input"))
      (node (ref "IC5") (pin "25") (pinfunction "A3_25") (pintype "input"))
      (node (ref "IC6") (pin "25") (pinfunction "A3_25") (pintype "input"))
    )
    (net (code "119") (name "Net-(IC13B-A)") (class "Default")
      (node (ref "IC13") (pin "13") (pinfunction "A_13") (pintype "input"))
      (node (ref "IC17") (pin "3") (pinfunction "O_3") (pintype "output"))
    )
    (net (code "120") (name "Net-(IC13B-QA)") (class "Default")
      (node (ref "IC13") (pin "11") (pinfunction "QA_11") (pintype "output"))
      (node (ref "IC5") (pin "26") (pinfunction "A4_26") (pintype "input"))
      (node (ref "IC6") (pin "26") (pinfunction "A4_26") (pintype "input"))
    )
    (net (code "121") (name "Net-(IC13B-QB)") (class "Default")
      (node (ref "IC13") (pin "10") (pinfunction "QB_10") (pintype "output"))
      (node (ref "IC5") (pin "1") (pinfunction "A5_1") (pintype "input"))
      (node (ref "IC6") (pin "1") (pinfunction "A5_1") (pintype "input"))
    )
    (net (code "122") (name "Net-(IC13B-QC)") (class "Default")
      (node (ref "IC13") (pin "9") (pinfunction "QC_9") (pintype "output"))
      (node (ref "IC5") (pin "2") (pinfunction "A6_2") (pintype "input"))
      (node (ref "IC6") (pin "2") (pinfunction "A6_2") (pintype "input"))
    )
    (net (code "123") (name "Net-(IC13B-QD)") (class "Default")
      (node (ref "IC13") (pin "8") (pinfunction "QD_8") (pintype "output"))
      (node (ref "IC5") (pin "3") (pinfunction "A7_3") (pintype "input"))
      (node (ref "IC6") (pin "3") (pinfunction "A7_3") (pintype "input"))
    )
    (net (code "124") (name "Net-(IC14A-A1)") (class "Default")
      (node (ref "IC14") (pin "2") (pinfunction "A1_2") (pintype "input"))
      (node (ref "IC5") (pin "11") (pinfunction "DQ0_11") (pintype "bidirectional"))
    )
    (net (code "125") (name "Net-(IC14A-A2)") (class "Default")
      (node (ref "IC14") (pin "3") (pinfunction "A2_3") (pintype "input"))
      (node (ref "IC5") (pin "12") (pinfunction "DQ1_12") (pintype "bidirectional"))
    )
    (net (code "126") (name "Net-(IC14A-A3)") (class "Default")
      (node (ref "IC14") (pin "4") (pinfunction "A3_4") (pintype "input"))
      (node (ref "IC5") (pin "13") (pinfunction "DQ2_13") (pintype "bidirectional"))
    )
    (net (code "127") (name "Net-(IC14A-A4)") (class "Default")
      (node (ref "IC14") (pin "5") (pinfunction "A4_5") (pintype "input"))
      (node (ref "IC5") (pin "15") (pinfunction "DQ3_15") (pintype "bidirectional"))
    )
    (net (code "128") (name "Net-(IC14A-A5)") (class "Default")
      (node (ref "IC14") (pin "6") (pinfunction "A5_6") (pintype "input"))
      (node (ref "IC5") (pin "16") (pinfunction "DQ4_16") (pintype "bidirectional"))
    )
    (net (code "129") (name "Net-(IC14A-A6)") (class "Default")
      (node (ref "IC14") (pin "7") (pinfunction "A6_7") (pintype "input"))
      (node (ref "IC5") (pin "17") (pinfunction "DQ5_17") (pintype "bidirectional"))
    )
    (net (code "130") (name "Net-(IC14A-A7)") (class "Default")
      (node (ref "IC14") (pin "8") (pinfunction "A7_8") (pintype "input"))
      (node (ref "IC5") (pin "18") (pinfunction "DQ6_18") (pintype "bidirectional"))
    )
    (net (code "131") (name "Net-(IC14A-A8)") (class "Default")
      (node (ref "IC14") (pin "9") (pinfunction "A8_9") (pintype "input"))
      (node (ref "IC5") (pin "19") (pinfunction "DQ7_19") (pintype "bidirectional"))
    )
    (net (code "132") (name "Net-(IC14A-G2)") (class "Default")
      (node (ref "IC14") (pin "19") (pinfunction "G2_19") (pintype "input"))
      (node (ref "IC8") (pin "8") (pinfunction "O_8") (pintype "output"))
    )
    (net (code "133") (name "Net-(IC14A-Y1)") (class "Default")
      (node (ref "D1") (pin "A") (pinfunction "A_A") (pintype "passive"))
      (node (ref "D9") (pin "A") (pinfunction "A_A") (pintype "passive"))
      (node (ref "IC14") (pin "18") (pinfunction "Y1_18") (pintype "tri_state"))
      (node (ref "IC18") (pin "18") (pinfunction "Y1_18") (pintype "tri_state"))
      (node (ref "R38") (pin "2") (pinfunction "2_2") (pintype "passive"))
    )
    (net (code "134") (name "Net-(IC14A-Y2)") (class "Default")
      (node (ref "D10") (pin "A") (pinfunction "A_A") (pintype "passive"))
      (node (ref "D2") (pin "A") (pinfunction "A_A") (pintype "passive"))
      (node (ref "IC14") (pin "17") (pinfunction "Y2_17") (pintype "tri_state"))
      (node (ref "IC18") (pin "17") (pinfunction "Y2_17") (pintype "tri_state"))
      (node (ref "R37") (pin "2") (pinfunction "2_2") (pintype "passive"))
    )
    (net (code "135") (name "Net-(IC14A-Y3)") (class "Default")
      (node (ref "D11") (pin "A") (pinfunction "A_A") (pintype "passive"))
      (node (ref "D3") (pin "A") (pinfunction "A_A") (pintype "passive"))
      (node (ref "IC14") (pin "16") (pinfunction "Y3_16") (pintype "tri_state"))
      (node (ref "IC18") (pin "16") (pinfunction "Y3_16") (pintype "tri_state"))
      (node (ref "R36") (pin "2") (pinfunction "2_2") (pintype "passive"))
    )
    (net (code "136") (name "Net-(IC14A-Y4)") (class "Default")
      (node (ref "D12") (pin "A") (pinfunction "A_A") (pintype "passive"))
      (node (ref "D4") (pin "A") (pinfunction "A_A") (pintype "passive"))
      (node (ref "IC14") (pin "15") (pinfunction "Y4_15") (pintype "tri_state"))
      (node (ref "IC18") (pin "15") (pinfunction "Y4_15") (pintype "tri_state"))
      (node (ref "R35") (pin "2") (pinfunction "2_2") (pintype "passive"))
    )
    (net (code "137") (name "Net-(IC14A-Y5)") (class "Default")
      (node (ref "D13") (pin "A") (pinfunction "A_A") (pintype "passive"))
      (node (ref "D5") (pin "A") (pinfunction "A_A") (pintype "passive"))
      (node (ref "IC14") (pin "14") (pinfunction "Y5_14") (pintype "tri_state"))
      (node (ref "IC18") (pin "14") (pinfunction "Y5_14") (pintype "tri_state"))
      (node (ref "R34") (pin "1") (pinfunction "1_1") (pintype "passive"))
    )
    (net (code "138") (name "Net-(IC14A-Y6)") (class "Default")
      (node (ref "D14") (pin "A") (pinfunction "A_A") (pintype "passive"))
      (node (ref "D6") (pin "A") (pinfunction "A_A") (pintype "passive"))
      (node (ref "IC14") (pin "13") (pinfunction "Y6_13") (pintype "tri_state"))
      (node (ref "IC18") (pin "13") (pinfunction "Y6_13") (pintype "tri_state"))
      (node (ref "R33") (pin "1") (pinfunction "1_1") (pintype "passive"))
    )
    (net (code "139") (name "Net-(IC14A-Y7)") (class "Default")
      (node (ref "D15") (pin "A") (pinfunction "A_A") (pintype "passive"))
      (node (ref "D7") (pin "A") (pinfunction "A_A") (pintype "passive"))
      (node (ref "IC14") (pin "12") (pinfunction "Y7_12") (pintype "tri_state"))
      (node (ref "IC18") (pin "12") (pinfunction "Y7_12") (pintype "tri_state"))
      (node (ref "R32") (pin "1") (pinfunction "1_1") (pintype "passive"))
    )
    (net (code "140") (name "Net-(IC14A-Y8)") (class "Default")
      (node (ref "D16") (pin "A") (pinfunction "A_A") (pintype "passive"))
      (node (ref "D8") (pin "A") (pinfunction "A_A") (pintype "passive"))
      (node (ref "IC14") (pin "11") (pinfunction "Y8_11") (pintype "tri_state"))
      (node (ref "IC18") (pin "11") (pinfunction "Y8_11") (pintype "tri_state"))
      (node (ref "R31") (pin "2") (pinfunction "2_2") (pintype "passive"))
    )
    (net (code "141") (name "Net-(IC15A-I0)") (class "Default")
      (node (ref "IC15") (pin "1") (pinfunction "I0_1") (pintype "input"))
      (node (ref "IC2") (pin "11") (pinfunction "CLK_11") (pintype "input"))
      (node (ref "IC7") (pin "10") (pinfunction "S2_10") (pintype "output"))
    )
    (net (code "142") (name "Net-(IC15A-I1)") (class "Default")
      (node (ref "IC15") (pin "2") (pinfunction "I1_2") (pintype "input"))
      (node (ref "IC15") (pin "5") (pinfunction "I1_5") (pintype "input"))
      (node (ref "IC7") (pin "11") (pinfunction "S0_11") (pintype "output"))
    )
    (net (code "143") (name "Net-(IC15A-O)") (class "Default")
      (node (ref "IC15") (pin "3") (pinfunction "O_3") (pintype "output"))
      (node (ref "IC8") (pin "9") (pinfunction "I_9") (pintype "input"))
    )
    (net (code "144") (name "Net-(IC15B-I0)") (class "Default")
      (node (ref "IC15") (pin "4") (pinfunction "I0_4") (pintype "input"))
      (node (ref "IC7") (pin "5") (pinfunction "S6_5") (pintype "output"))
      (node (ref "IC8") (pin "13") (pinfunction "I_13") (pintype "input"))
    )
    (net (code "145") (name "Net-(IC15B-O)") (class "Default")
      (node (ref "IC1") (pin "11") (pinfunction "CLK_11") (pintype "input"))
      (node (ref "IC15") (pin "6") (pinfunction "O_6") (pintype "output"))
    )
    (net (code "146") (name "Net-(IC15C-O)") (class "Default")
      (node (ref "IC15") (pin "8") (pinfunction "O_8") (pintype "output"))
      (node (ref "IC17") (pin "2") (pinfunction "I1_2") (pintype "input"))
    )
    (net (code "147") (name "Net-(IC15D-O)") (class "Default")
      (node (ref "IC15") (pin "11") (pinfunction "O_11") (pintype "output"))
      (node (ref "IC17") (pin "1") (pinfunction "I0_1") (pintype "input"))
    )
    (net (code "148") (name "Net-(IC16-CON)") (class "Default")
      (node (ref "C2") (pin "1") (pinfunction "1_1") (pintype "passive"))
      (node (ref "IC16") (pin "5") (pinfunction "CON_5") (pintype "input"))
    )
    (net (code "149") (name "Net-(IC16-DIS)") (class "Default")
      (node (ref "IC16") (pin "7") (pinfunction "DIS_7") (pintype "input"))
      (node (ref "R28") (pin "1") (pinfunction "1_1") (pintype "passive"))
      (node (ref "R29") (pin "2") (pinfunction "2_2") (pintype "passive"))
    )
    (net (code "150") (name "Net-(IC16-OUT)") (class "Default")
      (node (ref "IC16") (pin "3") (pinfunction "OUT_3") (pintype "output"))
      (node (ref "IC8") (pin "11") (pinfunction "I_11") (pintype "input"))
    )
    (net (code "151") (name "Net-(IC16-TRE)") (class "Default")
      (node (ref "C1") (pin "1") (pinfunction "1_1") (pintype "passive"))
      (node (ref "IC16") (pin "2") (pinfunction "TRI_2") (pintype "input"))
      (node (ref "IC16") (pin "6") (pinfunction "TRE_6") (pintype "input"))
      (node (ref "R30") (pin "1") (pinfunction "1_1") (pintype "passive"))
    )
    (net (code "152") (name "Net-(IC18A-A1)") (class "Default")
      (node (ref "IC18") (pin "2") (pinfunction "A1_2") (pintype "input"))
      (node (ref "LED8") (pin "A") (pinfunction "A_A") (pintype "passive"))
      (node (ref "R27") (pin "2") (pinfunction "2_2") (pintype "passive"))
    )
    (net (code "153") (name "Net-(IC18A-A2)") (class "Default")
      (node (ref "IC18") (pin "3") (pinfunction "A2_3") (pintype "input"))
      (node (ref "LED7") (pin "A") (pinfunction "A_A") (pintype "passive"))
      (node (ref "R26") (pin "2") (pinfunction "2_2") (pintype "passive"))
    )
    (net (code "154") (name "Net-(IC18A-A3)") (class "Default")
      (node (ref "IC18") (pin "4") (pinfunction "A3_4") (pintype "input"))
      (node (ref "LED6") (pin "A") (pinfunction "A_A") (pintype "passive"))
      (node (ref "R25") (pin "2") (pinfunction "2_2") (pintype "passive"))
    )
    (net (code "155") (name "Net-(IC18A-A4)") (class "Default")
      (node (ref "IC18") (pin "5") (pinfunction "A4_5") (pintype "input"))
      (node (ref "LED5") (pin "A") (pinfunction "A_A") (pintype "passive"))
      (node (ref "R24") (pin "2") (pinfunction "2_2") (pintype "passive"))
    )
    (net (code "156") (name "Net-(IC18A-A5)") (class "Default")
      (node (ref "IC18") (pin "6") (pinfunction "A5_6") (pintype "input"))
      (node (ref "LED4") (pin "A") (pinfunction "A_A") (pintype "passive"))
      (node (ref "R23") (pin "2") (pinfunction "2_2") (pintype "passive"))
    )
    (net (code "157") (name "Net-(IC18A-A6)") (class "Default")
      (node (ref "IC18") (pin "7") (pinfunction "A6_7") (pintype "input"))
      (node (ref "LED3") (pin "A") (pinfunction "A_A") (pintype "passive"))
      (node (ref "R21") (pin "2") (pinfunction "2_2") (pintype "passive"))
    )
    (net (code "158") (name "Net-(IC18A-A7)") (class "Default")
      (node (ref "IC18") (pin "8") (pinfunction "A7_8") (pintype "input"))
      (node (ref "LED2") (pin "A") (pinfunction "A_A") (pintype "passive"))
      (node (ref "R22") (pin "2") (pinfunction "2_2") (pintype "passive"))
    )
    (net (code "159") (name "Net-(IC18A-A8)") (class "Default")
      (node (ref "IC18") (pin "9") (pinfunction "A8_9") (pintype "input"))
      (node (ref "LED1") (pin "A") (pinfunction "A_A") (pintype "passive"))
      (node (ref "R20") (pin "2") (pinfunction "2_2") (pintype "passive"))
    )
    (net (code "160") (name "Net-(IC18A-G2)") (class "Default")
      (node (ref "IC18") (pin "19") (pinfunction "G2_19") (pintype "input"))
      (node (ref "IC8") (pin "12") (pinfunction "O_12") (pintype "output"))
    )
    (net (code "161") (name "Net-(R29-Pad1)") (class "Default")
      (node (ref "R29") (pin "1") (pinfunction "1_1") (pintype "passive"))
      (node (ref "R30") (pin "2") (pinfunction "2_2") (pintype "passive"))
    )
    (net (code "162") (name "VCC") (class "Default")
      (node (ref "IC16") (pin "4") (pinfunction "/RES_4") (pintype "input"))
      (node (ref "IC16") (pin "8") (pinfunction "VCC+_8") (pintype "power_in"))
      (node (ref "IC5") (pin "27") (pinfunction "~{WE}_27") (pintype "input"))
      (node (ref "IC6") (pin "27") (pinfunction "~{WE}_27") (pintype "input"))
      (node (ref "IC7") (pin "23") (pinfunction "INH_23") (pintype "input"))
      (node (ref "R28") (pin "2") (pinfunction "2_2") (pintype "passive"))
    )
    (net (code "163") (name "unconnected-(GND-Pad1)") (class "Default")
      (node (ref "GND") (pin "1") (pinfunction "1_1") (pintype "passive"))
    )
    (net (code "164") (name "unconnected-(VCC-Pad1)") (class "Default")
      (node (ref "VCC") (pin "1") (pinfunction "1_1") (pintype "passive"))
    )
  )
)
